# Schematic.net
KiCad netlist of a schematic drawn in EasyEDA
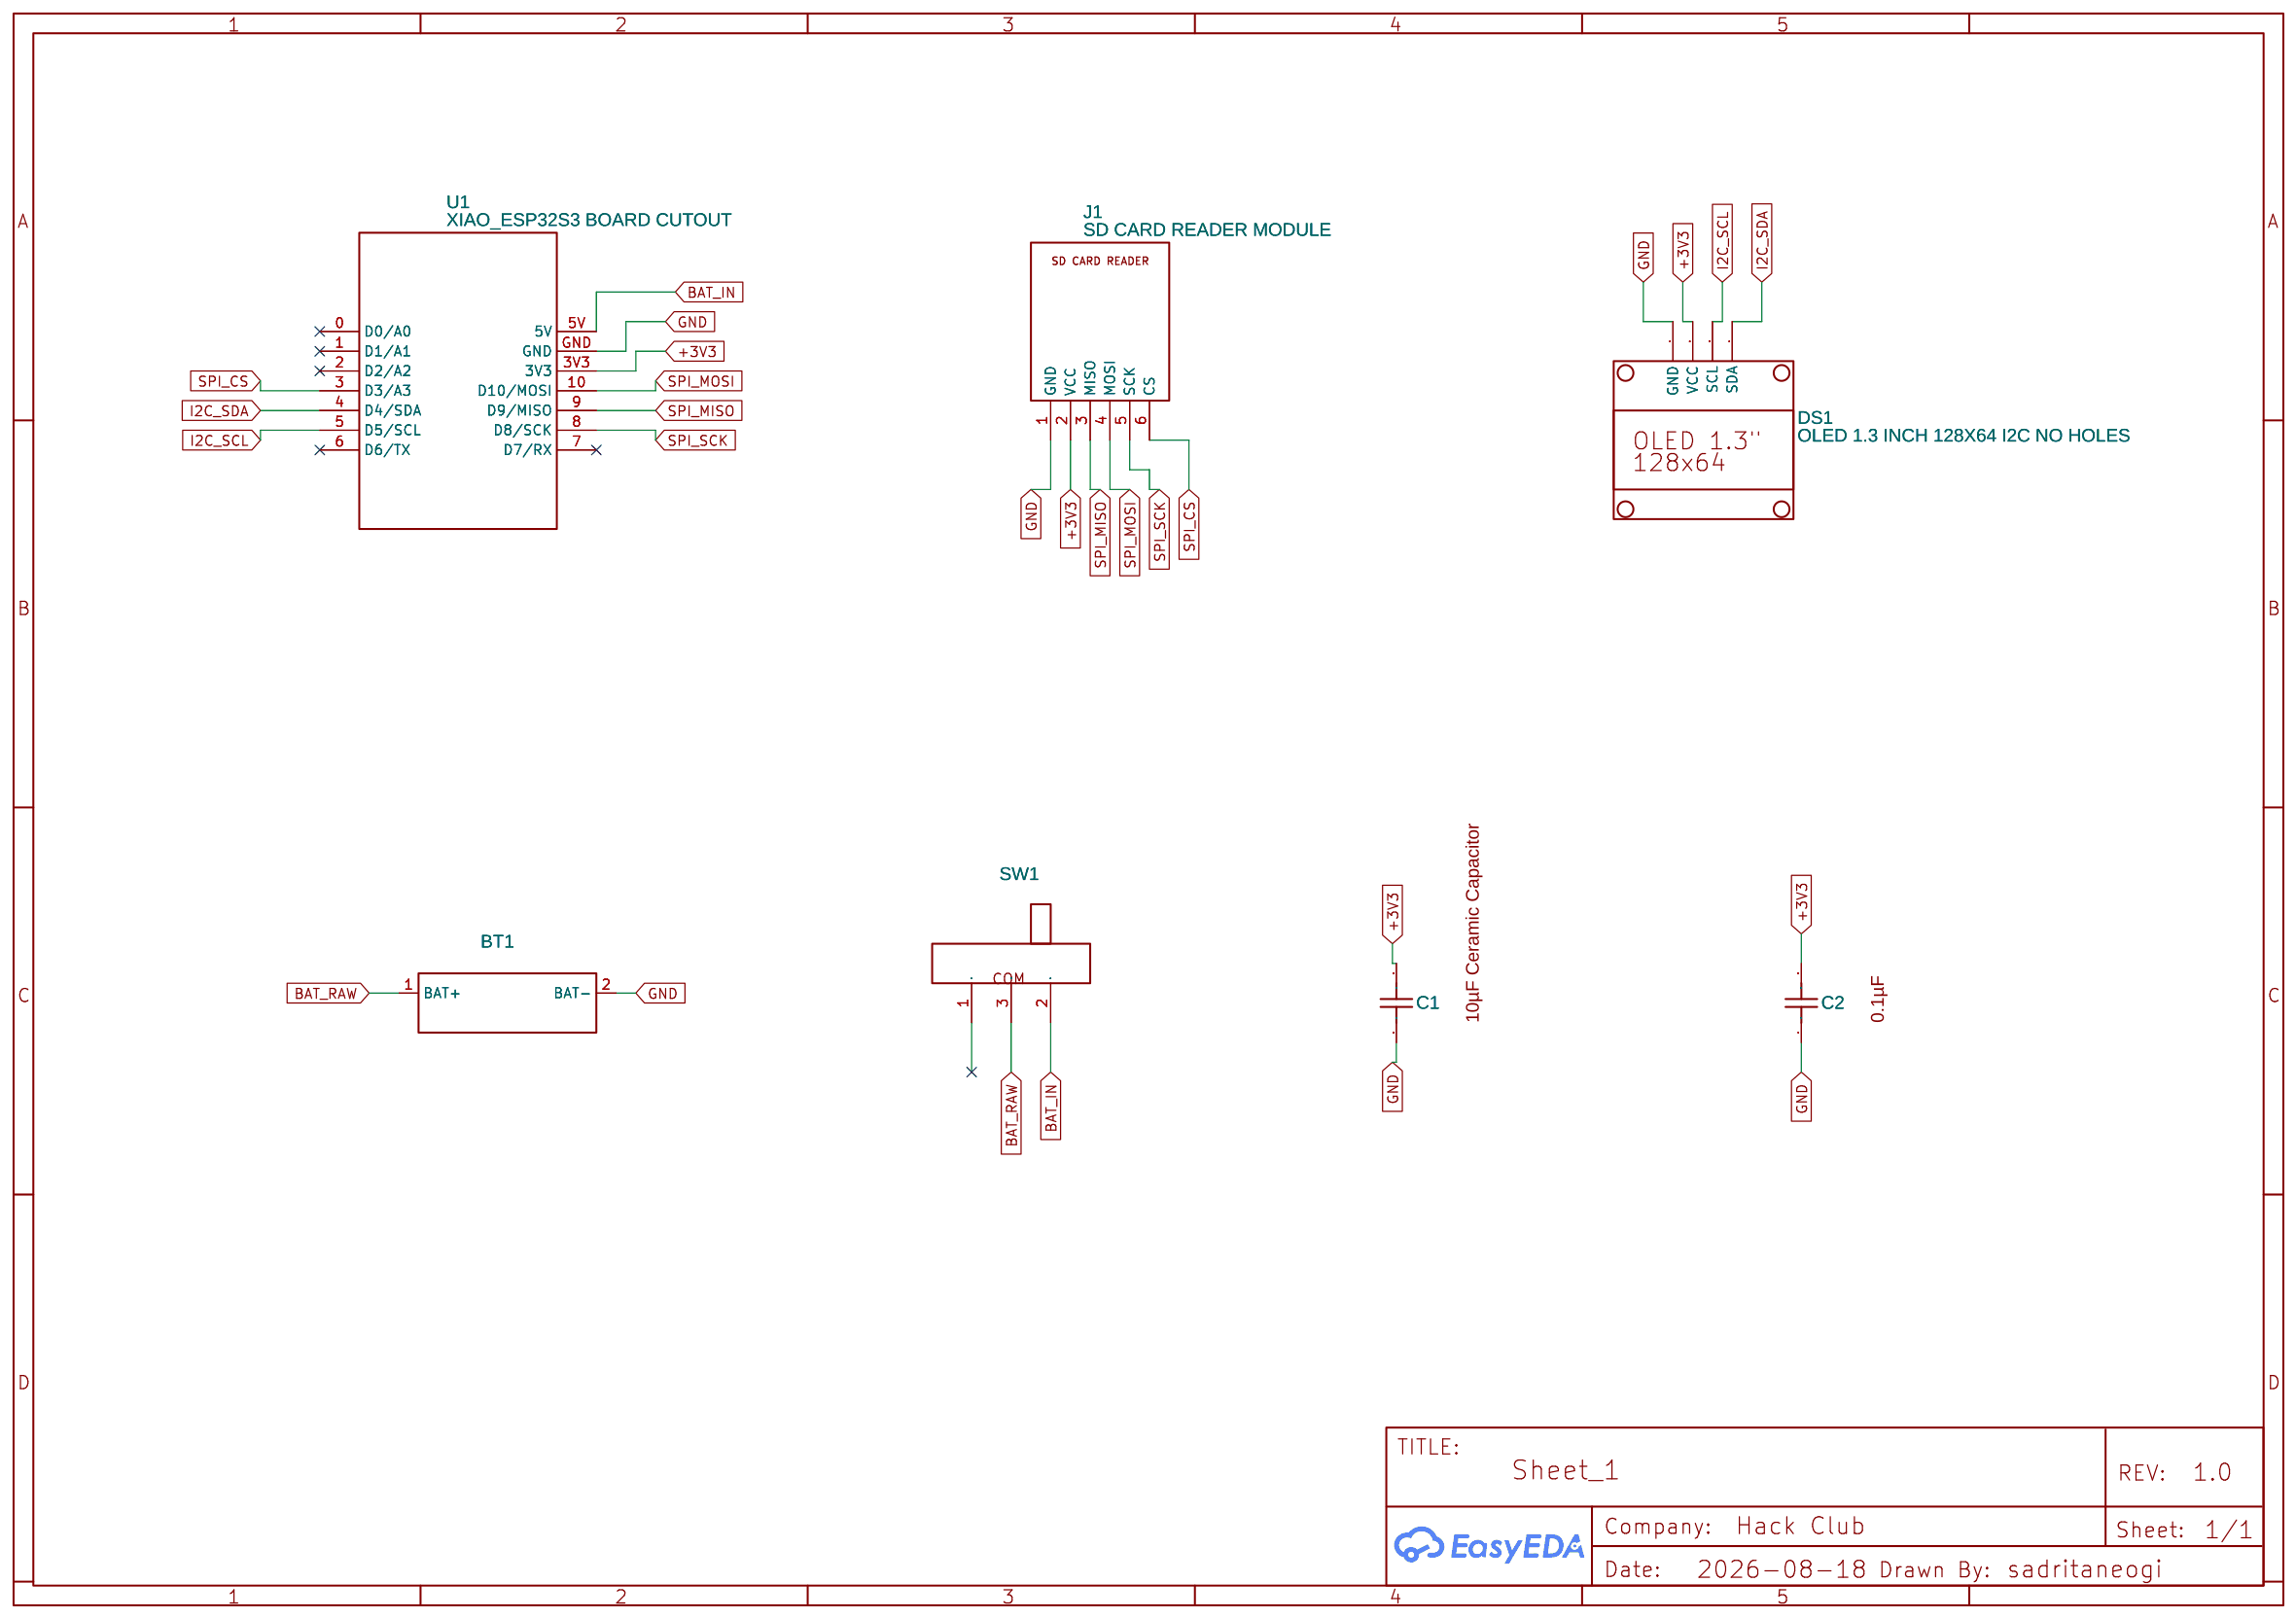
[diagram p0: schematic sheet]

(export (version "E")
  (design (tool "Eeschema 10.0.6"))
  (components
    (comp (ref "BT1")
      (value "BATTERY_PROVISION")
      (fields (field (name "Manufacturer Part") "2.54mm_1x2_Header") (field (name "Manufacturer") "Generic"))
      (libsource (lib "") (part "B2B-PH-K-S"))
    )
    (comp (ref "C1") (value "22pF Ceramic Capacitor") (libsource (lib "") (part "22pF Ceramic Capacitor_1")))
    (comp (ref "C2") (value "22pF Ceramic Capacitor") (libsource (lib "") (part "22pF Ceramic Capacitor")))
    (comp (ref "DS1")
      (value "OLED 1.3 INCH 128X64 I2C NO HOLES")
      (libsource (lib "") (part "OLED 1.3 INCH 128X64 I2C NO HOLES"))
    )
    (comp (ref "J1") (value "SD CARD READER MODULE") (libsource (lib "") (part "SD CARD READER MODULE")))
    (comp (ref "SW1")
      (value "Mini Power Switch - SPDT")
      (fields (field (name "Manufacturer") "E-Switch"))
      (libsource (lib "") (part "Mini Power Switch - SPDT"))
    )
    (comp (ref "U1")
      (value "XIAO_ESP32S3 BOARD CUTOUT")
      (fields (field (name "Manufacturer Part") "XIAO ESP32C3") (field (name "Manufacturer") "SeeedStudio"))
      (libsource (lib "") (part "XIAO_ESP32S3 BOARD CUTOUT"))
    )
  )
  (nets
    (net (code "1") (name "+3V3") (class "Default")
      (node (ref "C1") (pin "2") (pinfunction "2_2") (pintype "unspecified"))
      (node (ref "C2") (pin "2") (pinfunction "2_2") (pintype "unspecified"))
      (node (ref "DS1") (pin "2") (pinfunction "VCC_2") (pintype "unspecified"))
      (node (ref "J1") (pin "2") (pinfunction "VCC_2") (pintype "unspecified"))
      (node (ref "U1") (pin "3V3") (pinfunction "3V3_3V3") (pintype "unspecified"))
    )
    (net (code "2") (name "BAT_IN") (class "Default")
      (node (ref "SW1") (pin "2") (pinfunction "2_2") (pintype "unspecified"))
      (node (ref "U1") (pin "5V") (pinfunction "5V_5V") (pintype "unspecified"))
    )
    (net (code "3") (name "BAT_RAW") (class "Default")
      (node (ref "BT1") (pin "1") (pinfunction "BAT+_1") (pintype "unspecified"))
      (node (ref "SW1") (pin "3") (pinfunction "COM_3") (pintype "unspecified"))
    )
    (net (code "4") (name "GND") (class "Default")
      (node (ref "BT1") (pin "2") (pinfunction "BAT-_2") (pintype "unspecified"))
      (node (ref "C1") (pin "1") (pinfunction "1_1") (pintype "unspecified"))
      (node (ref "C2") (pin "1") (pinfunction "1_1") (pintype "unspecified"))
      (node (ref "DS1") (pin "1") (pinfunction "GND_1") (pintype "unspecified"))
      (node (ref "J1") (pin "1") (pinfunction "GND_1") (pintype "unspecified"))
      (node (ref "U1") (pin "GND") (pinfunction "GND_GND") (pintype "unspecified"))
    )
    (net (code "5") (name "I2C_SCL") (class "Default")
      (node (ref "DS1") (pin "3") (pinfunction "SCL_3") (pintype "unspecified"))
      (node (ref "U1") (pin "5") (pinfunction "D5/SCL_5") (pintype "unspecified"))
    )
    (net (code "6") (name "I2C_SDA") (class "Default")
      (node (ref "DS1") (pin "4") (pinfunction "SDA_4") (pintype "unspecified"))
      (node (ref "U1") (pin "4") (pinfunction "D4/SDA_4") (pintype "unspecified"))
    )
    (net (code "7") (name "SPI_CS") (class "Default")
      (node (ref "J1") (pin "6") (pinfunction "CS_6") (pintype "unspecified"))
      (node (ref "U1") (pin "3") (pinfunction "D3/A3_3") (pintype "unspecified"))
    )
    (net (code "8") (name "SPI_MISO") (class "Default")
      (node (ref "J1") (pin "3") (pinfunction "MISO_3") (pintype "unspecified"))
      (node (ref "U1") (pin "9") (pinfunction "D9/MISO_9") (pintype "unspecified"))
    )
    (net (code "9") (name "SPI_MOSI") (class "Default")
      (node (ref "J1") (pin "4") (pinfunction "MOSI_4") (pintype "unspecified"))
      (node (ref "U1") (pin "10") (pinfunction "D10/MOSI_10") (pintype "unspecified"))
    )
    (net (code "10") (name "SPI_SCK") (class "Default")
      (node (ref "J1") (pin "5") (pinfunction "SCK_5") (pintype "unspecified"))
      (node (ref "U1") (pin "8") (pinfunction "D8/SCK_8") (pintype "unspecified"))
    )
    (net (code "11") (name "unconnected-(SW1-Pad1)") (class "Default")
      (node (ref "SW1") (pin "1") (pinfunction "1_1") (pintype "unspecified+no_connect"))
    )
    (net (code "12") (name "unconnected-(U1-D0{slash}A0-Pad0)") (class "Default")
      (node (ref "U1") (pin "0") (pinfunction "D0/A0_0") (pintype "unspecified+no_connect"))
    )
    (net (code "13") (name "unconnected-(U1-D1{slash}A1-Pad1)") (class "Default")
      (node (ref "U1") (pin "1") (pinfunction "D1/A1_1") (pintype "unspecified+no_connect"))
    )
    (net (code "14") (name "unconnected-(U1-D2{slash}A2-Pad2)") (class "Default")
      (node (ref "U1") (pin "2") (pinfunction "D2/A2_2") (pintype "unspecified+no_connect"))
    )
    (net (code "15") (name "unconnected-(U1-D6{slash}TX-Pad6)") (class "Default")
      (node (ref "U1") (pin "6") (pinfunction "D6/TX_6") (pintype "unspecified+no_connect"))
    )
    (net (code "16") (name "unconnected-(U1-D7{slash}RX-Pad7)") (class "Default")
      (node (ref "U1") (pin "7") (pinfunction "D7/RX_7") (pintype "unspecified+no_connect"))
    )
  )
)
